# basic-inline-turbidimeter_rtc_board_v1.net
KiCad netlist of a schematic drawn in EAGLE
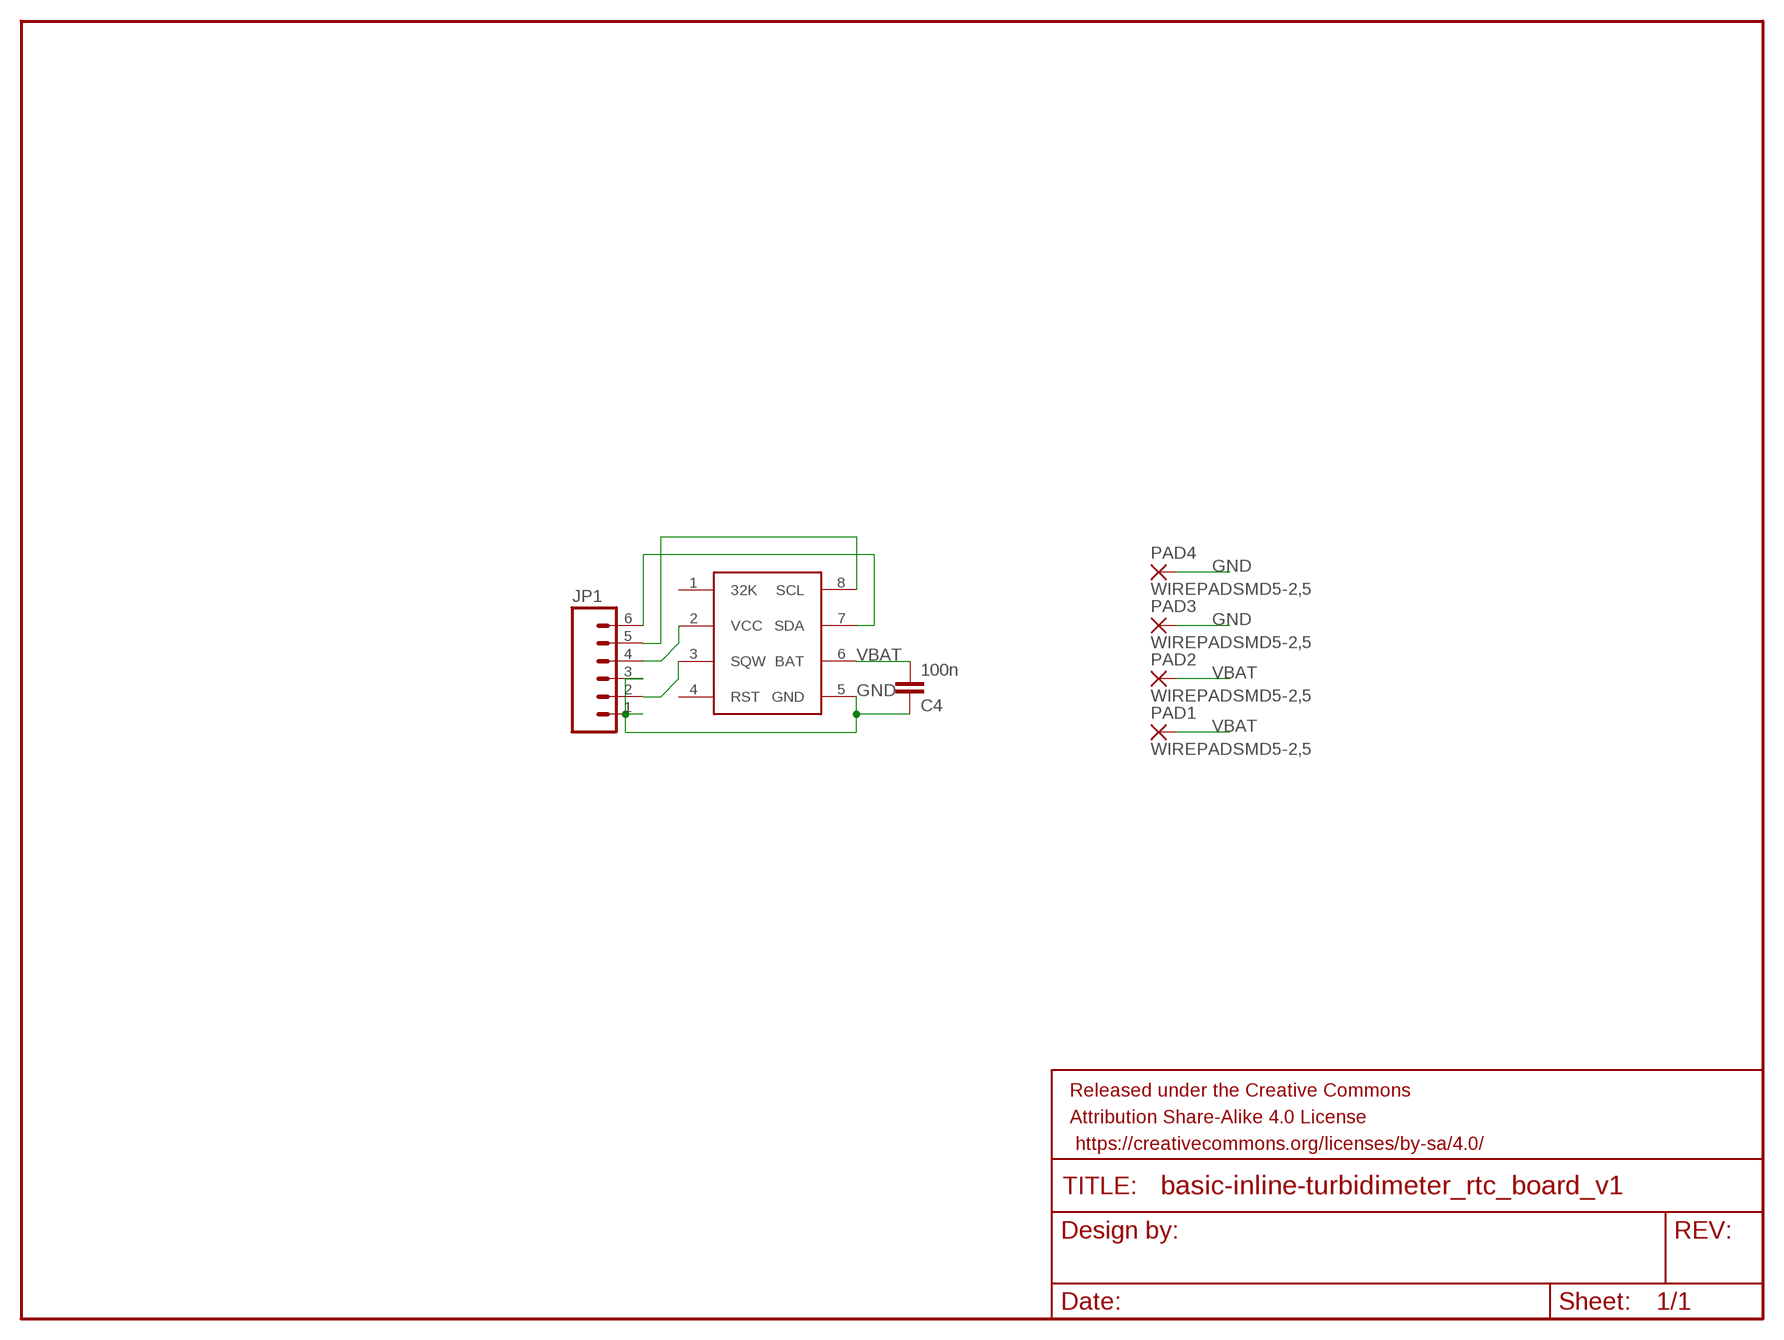
[diagram p0: schematic, sheet 1]

(export (version "E")
  (design (tool "Eeschema 10.0.6"))
  (components
    (comp (ref "*RTC")
      (value "DS3231M")
      (footprint "eagle-import:DS3231M")
      (libsource (lib "eagle-import") (part "DS3231M"))
    )
    (comp (ref "C4")
      (value "100n")
      (footprint "eagle-import:0603-CAP")
      (libsource (lib "eagle-import") (part "CAP0603-CAP"))
    )
    (comp (ref "FRAME1")
      (value "FRAME-LETTER")
      (footprint "eagle-import:CREATIVE_COMMONS")
      (libsource (lib "eagle-import") (part "FRAME-LETTER"))
    )
    (comp (ref "JP1")
      (value "M06SILK_FEMALE_PTH")
      (footprint "eagle-import:1X06")
      (libsource (lib "eagle-import") (part "M06SILK_FEMALE_PTH"))
    )
    (comp (ref "PAD1")
      (value "WIREPADSMD5-2,5")
      (footprint "eagle-import:5-2,5")
      (libsource (lib "eagle-import") (part "WIREPADSMD5-2,5"))
    )
    (comp (ref "PAD2")
      (value "WIREPADSMD5-2,5")
      (footprint "eagle-import:5-2,5")
      (libsource (lib "eagle-import") (part "WIREPADSMD5-2,5"))
    )
    (comp (ref "PAD3")
      (value "WIREPADSMD5-2,5")
      (footprint "eagle-import:5-2,5")
      (libsource (lib "eagle-import") (part "WIREPADSMD5-2,5"))
    )
    (comp (ref "PAD4")
      (value "WIREPADSMD5-2,5")
      (footprint "eagle-import:5-2,5")
      (libsource (lib "eagle-import") (part "WIREPADSMD5-2,5"))
    )
  )
  (nets
    (net (code "1") (name "/GND") (class "Default")
      (node (ref "*RTC") (pin "5") (pinfunction "GND_5") (pintype "bidirectional"))
      (node (ref "C4") (pin "1") (pinfunction "1_1") (pintype "passive"))
      (node (ref "JP1") (pin "1") (pinfunction "1_1") (pintype "passive"))
      (node (ref "JP1") (pin "3") (pinfunction "3_3") (pintype "passive"))
      (node (ref "PAD3") (pin "1") (pinfunction "P_1") (pintype "passive"))
      (node (ref "PAD4") (pin "1") (pinfunction "P_1") (pintype "passive"))
    )
    (net (code "2") (name "/VBAT") (class "Default")
      (node (ref "*RTC") (pin "6") (pinfunction "BAT_6") (pintype "bidirectional"))
      (node (ref "C4") (pin "2") (pinfunction "2_2") (pintype "passive"))
      (node (ref "PAD1") (pin "1") (pinfunction "P_1") (pintype "passive"))
      (node (ref "PAD2") (pin "1") (pinfunction "P_1") (pintype "passive"))
    )
    (net (code "3") (name "Net-(*RTC-SCL)") (class "Default")
      (node (ref "*RTC") (pin "8") (pinfunction "SCL_8") (pintype "bidirectional"))
      (node (ref "JP1") (pin "5") (pinfunction "5_5") (pintype "passive"))
    )
    (net (code "4") (name "Net-(*RTC-SDA)") (class "Default")
      (node (ref "*RTC") (pin "7") (pinfunction "SDA_7") (pintype "bidirectional"))
      (node (ref "JP1") (pin "6") (pinfunction "6_6") (pintype "passive"))
    )
    (net (code "5") (name "Net-(*RTC-SQW)") (class "Default")
      (node (ref "*RTC") (pin "3") (pinfunction "SQW_3") (pintype "bidirectional"))
      (node (ref "JP1") (pin "2") (pinfunction "2_2") (pintype "passive"))
    )
    (net (code "6") (name "Net-(*RTC-VCC)") (class "Default")
      (node (ref "*RTC") (pin "2") (pinfunction "VCC_2") (pintype "bidirectional"))
      (node (ref "JP1") (pin "4") (pinfunction "4_4") (pintype "passive"))
    )
    (net (code "7") (name "unconnected-(*RTC-32K-Pad1)") (class "Default")
      (node (ref "*RTC") (pin "1") (pinfunction "32K_1") (pintype "bidirectional"))
    )
    (net (code "8") (name "unconnected-(*RTC-RST-Pad4)") (class "Default")
      (node (ref "*RTC") (pin "4") (pinfunction "RST_4") (pintype "bidirectional"))
    )
  )
)
